# 5V_REG.net
KiCad netlist of a schematic drawn in Altium Designer
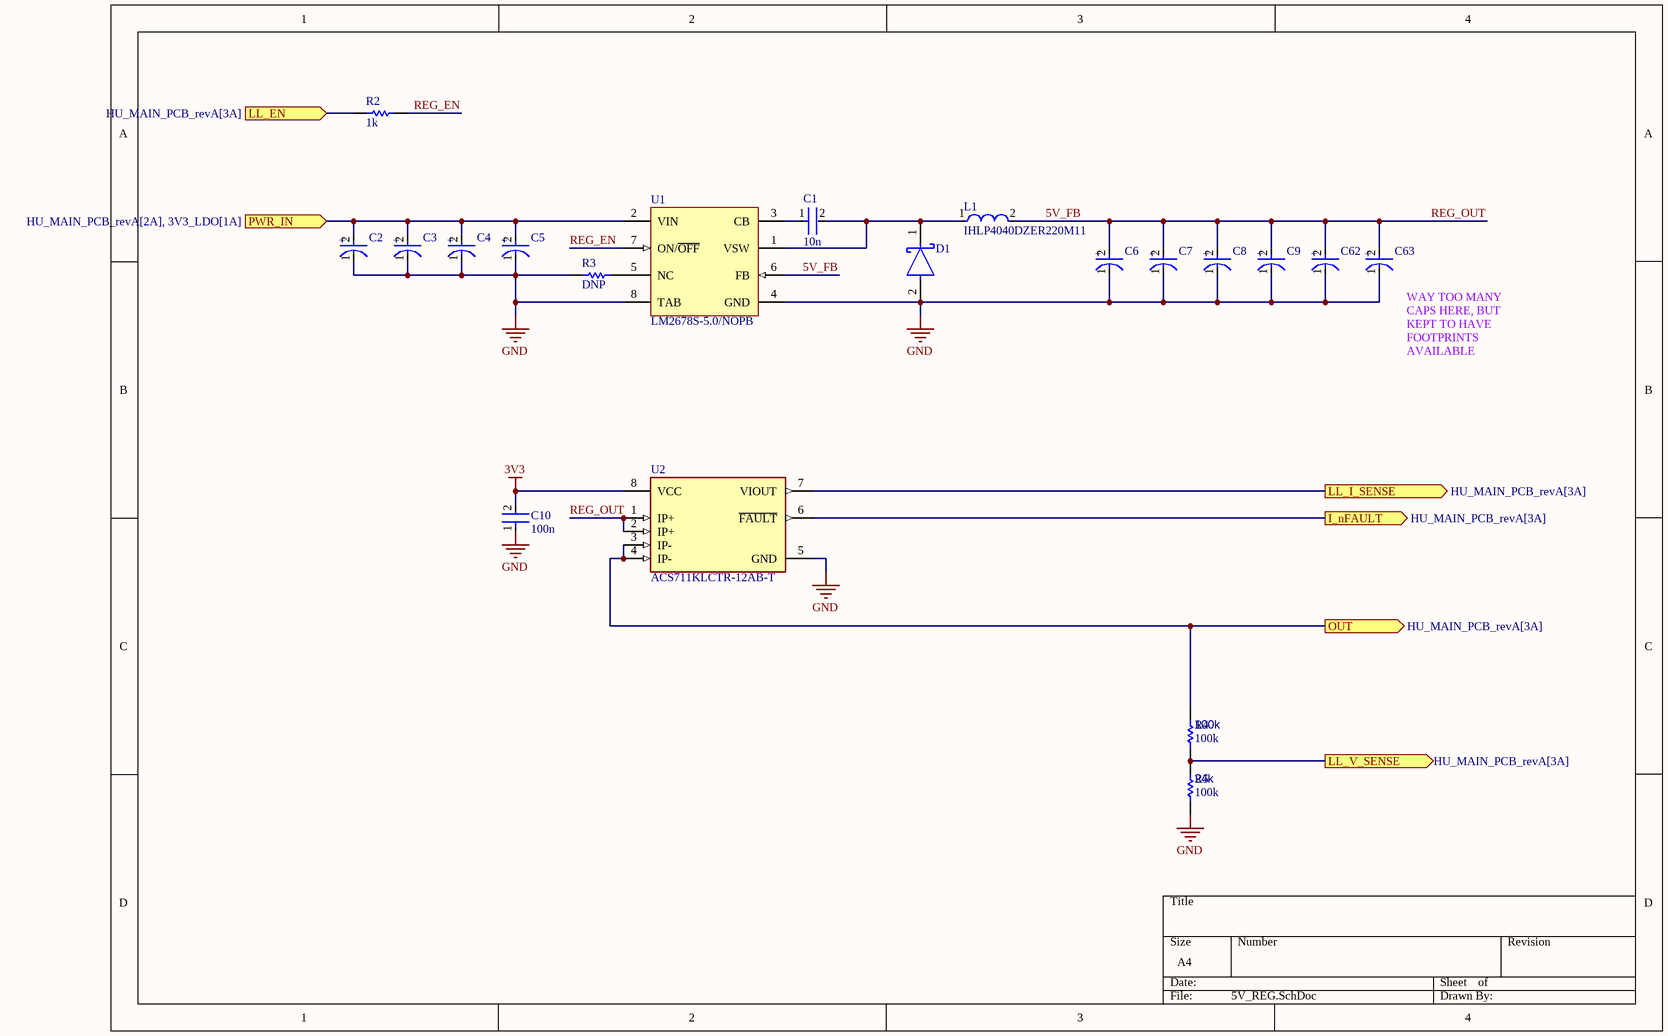
[diagram p0: 5V_REG.SchDoc]

(export (version "E")
  (design (tool "Eeschema 10.0.6"))
  (components
    (comp (ref "C1")
      (value "10n")
      (footprint "FP-0402-L_1_0_0_05-W_0_5-IPC_A")
      (description "LARGE PADS, 0402 CAP, CHANGE COMMENT TO MATCH REAL P/N")
      (libsource (lib "Space Concordia") (part "b4654b650e69147ec39a6b967a45e02"))
    )
    (comp (ref "C2")
      (value "TPSE686K025R0125")
      (footprint "FP-TPSE-MFG")
      (description "CAP TANT 68UF 10% 25V 2917")
      (fields (field (name "VOLTAGE") "25V") (field (name "TOLERANCE") "10%"))
      (libsource (lib "Altium Content Vault") (part "203bc49f2ac43e59fd269a8c329ed05"))
    )
    (comp (ref "C3")
      (value "TPSE686K025R0125")
      (footprint "FP-TPSE-MFG")
      (description "CAP TANT 68UF 10% 25V 2917")
      (fields (field (name "VOLTAGE") "25V") (field (name "TOLERANCE") "10%"))
      (libsource (lib "Altium Content Vault") (part "203bc49f2ac43e59fd269a8c329ed05"))
    )
    (comp (ref "C4")
      (value "TPSE686K025R0125")
      (footprint "FP-TPSE-MFG")
      (description "CAP TANT 68UF 10% 25V 2917")
      (fields (field (name "VOLTAGE") "25V") (field (name "TOLERANCE") "10%"))
      (libsource (lib "Altium Content Vault") (part "203bc49f2ac43e59fd269a8c329ed05"))
    )
    (comp (ref "C5")
      (value "TPSE686K025R0125")
      (footprint "FP-TPSE-MFG")
      (description "CAP TANT 68UF 10% 25V 2917")
      (fields (field (name "VOLTAGE") "25V") (field (name "TOLERANCE") "10%"))
      (libsource (lib "Altium Content Vault") (part "203bc49f2ac43e59fd269a8c329ed05"))
    )
    (comp (ref "C6")
      (value "TPSE686K025R0125")
      (footprint "FP-TPSE-MFG")
      (description "CAP TANT 68UF 10% 25V 2917")
      (fields (field (name "VOLTAGE") "25V") (field (name "TOLERANCE") "10%"))
      (libsource (lib "Altium Content Vault") (part "203bc49f2ac43e59fd269a8c329ed05"))
    )
    (comp (ref "C7")
      (value "TPSE686K025R0125")
      (footprint "FP-TPSE-MFG")
      (description "CAP TANT 68UF 10% 25V 2917")
      (fields (field (name "VOLTAGE") "25V") (field (name "TOLERANCE") "10%"))
      (libsource (lib "Altium Content Vault") (part "203bc49f2ac43e59fd269a8c329ed05"))
    )
    (comp (ref "C8")
      (value "TPSE686K025R0125")
      (footprint "FP-TPSE-MFG")
      (description "CAP TANT 68UF 10% 25V 2917")
      (fields (field (name "VOLTAGE") "25V") (field (name "TOLERANCE") "10%"))
      (libsource (lib "Altium Content Vault") (part "203bc49f2ac43e59fd269a8c329ed05"))
    )
    (comp (ref "C9")
      (value "TPSE686K025R0125")
      (footprint "FP-TPSE-MFG")
      (description "CAP TANT 68UF 10% 25V 2917")
      (fields (field (name "VOLTAGE") "25V") (field (name "TOLERANCE") "10%"))
      (libsource (lib "Altium Content Vault") (part "203bc49f2ac43e59fd269a8c329ed05"))
    )
    (comp (ref "C10")
      (value "100n")
      (footprint "FP-0402-L_1_0_0_05-W_0_5-IPC_A")
      (description "LARGE PADS, 0402 CAP, CHANGE COMMENT TO MATCH REAL P/N")
      (libsource (lib "Space Concordia") (part "b4654b650e69147ec39a6b967a45e02"))
    )
    (comp (ref "C62")
      (value "TPSE686K025R0125")
      (footprint "FP-TPSE-MFG")
      (description "CAP TANT 68UF 10% 25V 2917")
      (fields (field (name "VOLTAGE") "25V") (field (name "TOLERANCE") "10%"))
      (libsource (lib "Altium Content Vault") (part "203bc49f2ac43e59fd269a8c329ed05"))
    )
    (comp (ref "C63")
      (value "TPSE686K025R0125")
      (footprint "FP-TPSE-MFG")
      (description "CAP TANT 68UF 10% 25V 2917")
      (fields (field (name "VOLTAGE") "25V") (field (name "TOLERANCE") "10%"))
      (libsource (lib "Altium Content Vault") (part "203bc49f2ac43e59fd269a8c329ed05"))
    )
    (comp (ref "D1")
      (value "B540C-13-F")
      (footprint "FP-SMC-MFG")
      (description "DIODE SCHOTTKY 40V 5A SMC")
      (fields
        (field (name "OCTOPART") "https://octopart.com/b540c-13-f-diodes+inc.-325873")
        (field (name "MANUFACTURER") "Diodes Inc.")
      )
      (libsource (lib "Altium Content Vault") (part "1d6ec82d83fb6aee721767c19dac4b9"))
    )
    (comp (ref "L1")
      (value "IHLP4040DZER220M11")
      (footprint "FP-IHLP-4040DZ-FP_3_124x3-MFG")
      (description "Commercial Inductors, Low DCR Series 22uH 5A 66mΩ 20%")
      (fields (field (name "TOLERANCE") "20%"))
      (libsource (lib "Altium Content Vault") (part "725321dda6339637d4d059423bc1c3c"))
    )
    (comp (ref "R2")
      (value "1k")
      (footprint "R0603B")
      (description "Resistor")
      (libsource (lib "Space Concordia") (part "Resistor"))
    )
    (comp (ref "R3")
      (value "DNP")
      (footprint "R0603B")
      (description "Resistor")
      (libsource (lib "Space Concordia") (part "Resistor"))
    )
    (comp (ref "R4")
      (value "100k")
      (footprint "R0603B")
      (description "Resistor")
      (fields (field (name "ALTIUM_VALUE") "100k"))
      (libsource (lib "Space Concordia") (part "Resistor"))
    )
    (comp (ref "R5")
      (value "100k")
      (footprint "R0603B")
      (description "Resistor")
      (fields (field (name "ALTIUM_VALUE") "24k"))
      (libsource (lib "Space Concordia") (part "Resistor"))
    )
    (comp (ref "U1")
      (value "LM2678S-5.0/NOPB")
      (footprint "KTW0007B_L")
      (description "SIMPLE SWITCHER® High Efficiency 5A Step-Down Voltage Regulator, 7-pin TO-263, Pb-Free")
      (fields (field (name "MANUFACTURER") "Texas Instruments"))
      (libsource (lib "Altium Content Vault") (part "PM-REG-LM2678S"))
    )
    (comp (ref "U2")
      (value "ACS711KLCTR-12AB-T")
      (footprint "FP-LC-8-IPC_C")
      (description "SENSOR CURRENT HALL 12.5A AC/DC")
      (libsource (lib "Altium Content Vault") (part "b5e82308d4912bad35d89a98a7a92f9"))
    )
  )
  (nets
    (net (code "1") (name "/5V_FB") (class "Default")
      (node (ref "C6") (pin "2") (pinfunction "A_2") (pintype "passive"))
      (node (ref "C62") (pin "2") (pinfunction "A_2") (pintype "passive"))
      (node (ref "C63") (pin "2") (pinfunction "A_2") (pintype "passive"))
      (node (ref "C7") (pin "2") (pinfunction "A_2") (pintype "passive"))
      (node (ref "C8") (pin "2") (pinfunction "A_2") (pintype "passive"))
      (node (ref "C9") (pin "2") (pinfunction "A_2") (pintype "passive"))
      (node (ref "L1") (pin "2") (pinfunction "2_2") (pintype "passive"))
      (node (ref "U1") (pin "6") (pinfunction "FB_6") (pintype "input"))
      (node (ref "U2") (pin "1") (pinfunction "IP+_1") (pintype "input"))
      (node (ref "U2") (pin "2") (pinfunction "IP+_2") (pintype "input"))
    )
    (net (code "2") (name "/I_nFAULT") (class "Default")
      (node (ref "U2") (pin "6") (pinfunction "~{FAULT}_6") (pintype "output"))
    )
    (net (code "3") (name "/LL_EN") (class "Default")
      (node (ref "R2") (pin "2") (pinfunction "2_2") (pintype "passive"))
    )
    (net (code "4") (name "/LL_I_SENSE") (class "Default")
      (node (ref "U2") (pin "7") (pinfunction "VIOUT_7") (pintype "output"))
    )
    (net (code "5") (name "/LL_V_SENSE") (class "Default")
      (node (ref "R4") (pin "1") (pinfunction "1_1") (pintype "passive"))
      (node (ref "R5") (pin "2") (pinfunction "2_2") (pintype "passive"))
    )
    (net (code "6") (name "/OUT") (class "Default")
      (node (ref "R4") (pin "2") (pinfunction "2_2") (pintype "passive"))
      (node (ref "U2") (pin "3") (pinfunction "IP-_3") (pintype "input"))
      (node (ref "U2") (pin "4") (pinfunction "IP-_4") (pintype "input"))
    )
    (net (code "7") (name "/PWR_IN") (class "Default")
      (node (ref "C2") (pin "2") (pinfunction "A_2") (pintype "passive"))
      (node (ref "C3") (pin "2") (pinfunction "A_2") (pintype "passive"))
      (node (ref "C4") (pin "2") (pinfunction "A_2") (pintype "passive"))
      (node (ref "C5") (pin "2") (pinfunction "A_2") (pintype "passive"))
      (node (ref "U1") (pin "2") (pinfunction "VIN_2") (pintype "power_in"))
    )
    (net (code "8") (name "/REG_EN") (class "Default")
      (node (ref "R2") (pin "1") (pinfunction "1_1") (pintype "passive"))
      (node (ref "U1") (pin "7") (pinfunction "ON/~{OFF}_7") (pintype "input"))
    )
    (net (code "9") (name "3V3") (class "Default")
      (node (ref "C10") (pin "2") (pinfunction "2_2") (pintype "passive"))
      (node (ref "U2") (pin "8") (pinfunction "VCC_8") (pintype "power_in"))
    )
    (net (code "10") (name "GND") (class "Default")
      (node (ref "C10") (pin "1") (pinfunction "1_1") (pintype "passive"))
      (node (ref "C2") (pin "1") (pinfunction "C_1") (pintype "passive"))
      (node (ref "C3") (pin "1") (pinfunction "C_1") (pintype "passive"))
      (node (ref "C4") (pin "1") (pinfunction "C_1") (pintype "passive"))
      (node (ref "C5") (pin "1") (pinfunction "C_1") (pintype "passive"))
      (node (ref "C6") (pin "1") (pinfunction "C_1") (pintype "passive"))
      (node (ref "C62") (pin "1") (pinfunction "C_1") (pintype "passive"))
      (node (ref "C63") (pin "1") (pinfunction "C_1") (pintype "passive"))
      (node (ref "C7") (pin "1") (pinfunction "C_1") (pintype "passive"))
      (node (ref "C8") (pin "1") (pinfunction "C_1") (pintype "passive"))
      (node (ref "C9") (pin "1") (pinfunction "C_1") (pintype "passive"))
      (node (ref "D1") (pin "2") (pinfunction "A_2") (pintype "passive"))
      (node (ref "R3") (pin "2") (pinfunction "2_2") (pintype "passive"))
      (node (ref "R5") (pin "1") (pinfunction "1_1") (pintype "passive"))
      (node (ref "U1") (pin "4") (pinfunction "GND_4") (pintype "power_in"))
      (node (ref "U1") (pin "8") (pinfunction "TAB_8") (pintype "power_in"))
      (node (ref "U2") (pin "5") (pinfunction "GND_5") (pintype "power_in"))
    )
    (net (code "11") (name "Net-(D1-C)") (class "Default")
      (node (ref "C1") (pin "2") (pinfunction "2_2") (pintype "passive"))
      (node (ref "D1") (pin "1") (pinfunction "C_1") (pintype "passive"))
      (node (ref "L1") (pin "1") (pinfunction "1_1") (pintype "passive"))
      (node (ref "U1") (pin "1") (pinfunction "VSW_1") (pintype "power_in"))
    )
    (net (code "12") (name "Net-(U1-CB)") (class "Default")
      (node (ref "C1") (pin "1") (pinfunction "1_1") (pintype "passive"))
      (node (ref "U1") (pin "3") (pinfunction "CB_3") (pintype "passive"))
    )
    (net (code "13") (name "Net-(U1-NC)") (class "Default")
      (node (ref "R3") (pin "1") (pinfunction "1_1") (pintype "passive"))
      (node (ref "U1") (pin "5") (pinfunction "NC_5") (pintype "passive"))
    )
  )
)
